# PolarTableMegaShield.net
KiCad netlist of a schematic drawn in EAGLE
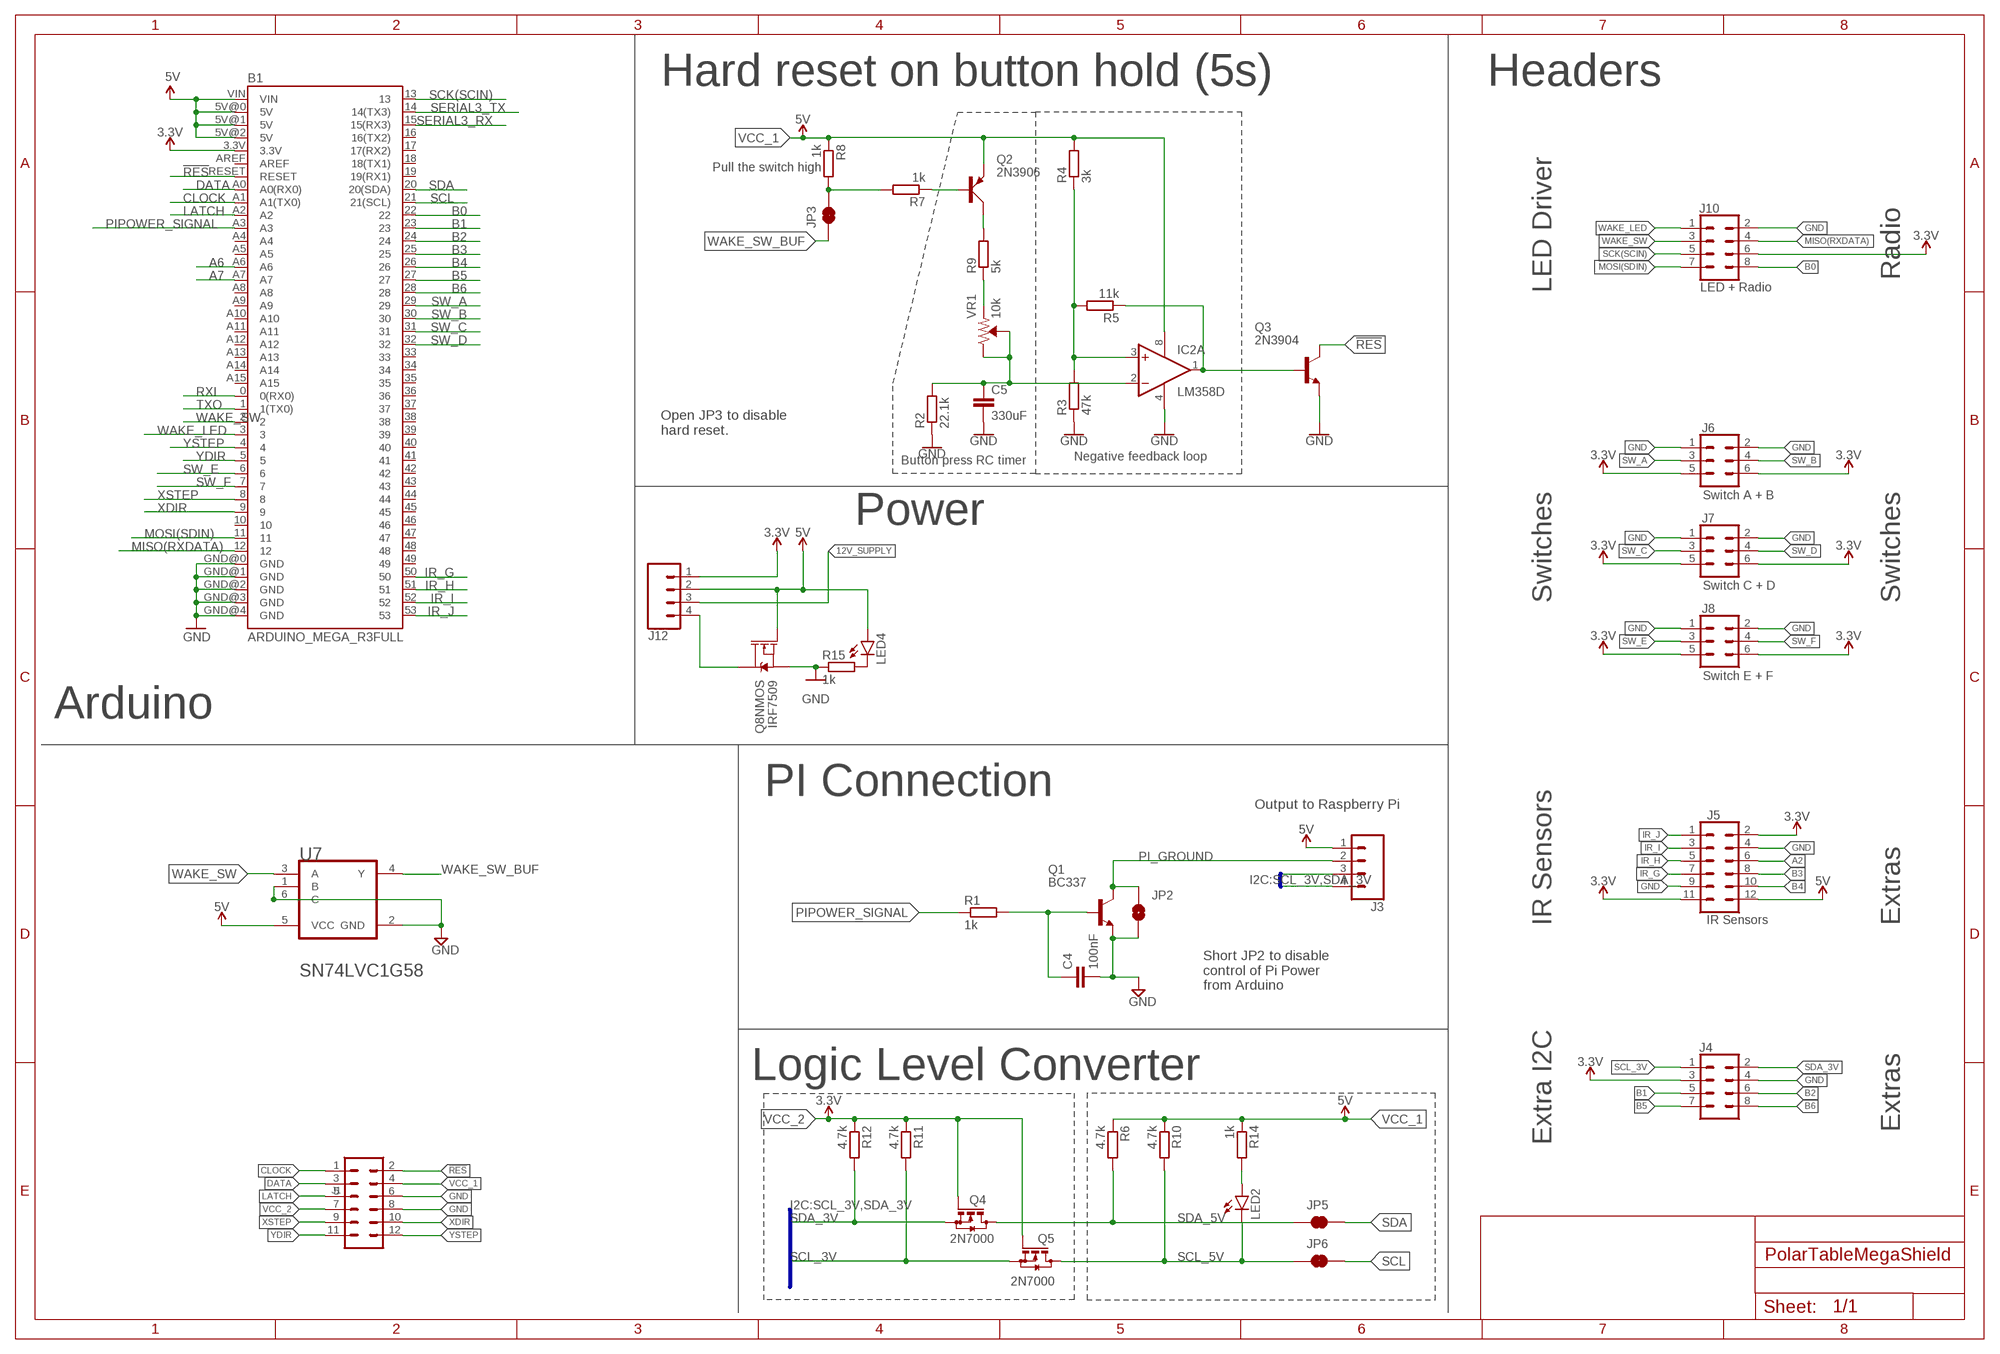
[diagram p0: schematic, sheet 1]

(export (version "E")
  (design (tool "Eeschema 10.0.6"))
  (components
    (comp (ref "B1")
      (value "ARDUINO_MEGA_R3FULL")
      (footprint "eagle-import:ARDUINO_MEGA")
      (libsource (lib "eagle-import") (part "ARDUINO_MEGA_R3FULL"))
    )
    (comp (ref "C4")
      (value "100nF")
      (footprint "eagle-import:C0805")
      (libsource (lib "eagle-import") (part "C-EUC0805"))
    )
    (comp (ref "C5")
      (value "330uF")
      (footprint "eagle-import:C0805")
      (libsource (lib "eagle-import") (part "C-EUC0805"))
    )
    (comp (ref "IC2")
      (value "LM358D")
      (footprint "eagle-import:SO08")
      (libsource (lib "eagle-import") (part "LM358D"))
    )
    (comp (ref "J1")
      (value "CONN_06X21.24MM_RA_MALE")
      (footprint "eagle-import:2X6")
      (libsource (lib "eagle-import") (part "CONN_06X21.24MM_RA_MALE"))
    )
    (comp (ref "J3")
      (value "Pi Connection")
      (footprint "eagle-import:1X04_1.24MM_RA_MALE")
      (libsource (lib "eagle-import") (part "CONN_041X04_1.24MM_RA_MALE"))
    )
    (comp (ref "J4")
      (value "CONN_04X22X4_1.24MM_RA_MALE")
      (footprint "eagle-import:2X4")
      (libsource (lib "eagle-import") (part "CONN_04X22X4_1.24MM_RA_MALE"))
    )
    (comp (ref "J5")
      (value "IR Sensors")
      (footprint "eagle-import:2X6")
      (libsource (lib "eagle-import") (part "CONN_06X21.24MM_RA_MALE"))
    )
    (comp (ref "J6")
      (value "Switch A + B")
      (footprint "eagle-import:2X3")
      (libsource (lib "eagle-import") (part "CONN_03X22X03_2.54MM_RA_MALE"))
    )
    (comp (ref "J7")
      (value "Switch C + D")
      (footprint "eagle-import:2X3")
      (libsource (lib "eagle-import") (part "CONN_03X22X03_2.54MM_RA_MALE"))
    )
    (comp (ref "J8")
      (value "Switch E + F")
      (footprint "eagle-import:2X3")
      (libsource (lib "eagle-import") (part "CONN_03X22X03_2.54MM_RA_MALE"))
    )
    (comp (ref "J10")
      (value "LED + Radio")
      (footprint "eagle-import:2X4")
      (libsource (lib "eagle-import") (part "CONN_04X22X4_1.24MM_RA_MALE"))
    )
    (comp (ref "J12")
      (value "CONN_04JST-PTH")
      (footprint "eagle-import:JST-4-PTH")
      (libsource (lib "eagle-import") (part "CONN_04JST-PTH"))
    )
    (comp (ref "JP2")
      (value "JUMPER-SMT_2_NO_SILK")
      (footprint "eagle-import:SMT-JUMPER_2_NO_SILK")
      (libsource (lib "eagle-import") (part "JUMPER-SMT_2_NO_SILK"))
    )
    (comp (ref "JP3")
      (value "Enable Hold to Reset")
      (footprint "eagle-import:SMT-JUMPER_2_NC_TRACE_SILK")
      (libsource (lib "eagle-import") (part "JUMPER-SMT_2_NC_TRACE_SILK"))
    )
    (comp (ref "JP5")
      (value "JUMPER-SMT_2_NC_TRACE_NO-SILK")
      (footprint "eagle-import:SMT-JUMPER_2_NC_TRACE_NO-SILK")
      (libsource (lib "eagle-import") (part "JUMPER-SMT_2_NC_TRACE_NO-SILK"))
    )
    (comp (ref "JP6")
      (value "JUMPER-SMT_2_NC_TRACE_NO-SILK")
      (footprint "eagle-import:SMT-JUMPER_2_NC_TRACE_NO-SILK")
      (libsource (lib "eagle-import") (part "JUMPER-SMT_2_NC_TRACE_NO-SILK"))
    )
    (comp (ref "LED2")
      (value "LEDCHIP-LED0805")
      (footprint "eagle-import:CHIP-LED0805")
      (libsource (lib "eagle-import") (part "LEDCHIP-LED0805"))
    )
    (comp (ref "LED4")
      (value "LEDCHIP-LED0805")
      (footprint "eagle-import:CHIP-LED0805")
      (libsource (lib "eagle-import") (part "LEDCHIP-LED0805"))
    )
    (comp (ref "Q1")
      (value "BC337")
      (footprint "eagle-import:TO92")
      (libsource (lib "eagle-import") (part "BC337"))
    )
    (comp (ref "Q2")
      (value "2N3906")
      (footprint "eagle-import:TO92D")
      (libsource (lib "eagle-import") (part "2N3906"))
    )
    (comp (ref "Q3")
      (value "2N3904")
      (footprint "eagle-import:TO92")
      (fields (field (name "NOTE") "Pull high until we get comparitor high output"))
      (libsource (lib "eagle-import") (part "2N3904"))
    )
    (comp (ref "Q4")
      (value "2N7000")
      (footprint "eagle-import:TO92-")
      (libsource (lib "eagle-import") (part "2N7000"))
    )
    (comp (ref "Q5")
      (value "2N7000")
      (footprint "eagle-import:TO92-")
      (libsource (lib "eagle-import") (part "2N7000"))
    )
    (comp (ref "Q8")
      (value "IRF7509")
      (footprint "eagle-import:MSOP8")
      (libsource (lib "eagle-import") (part "IRF7509"))
    )
    (comp (ref "R1")
      (value "1k")
      (footprint "eagle-import:M0805")
      (libsource (lib "eagle-import") (part "R-EU_M0805"))
    )
    (comp (ref "R2")
      (value "22.1k")
      (footprint "eagle-import:M0805")
      (libsource (lib "eagle-import") (part "R-EU_M0805"))
    )
    (comp (ref "R3")
      (value "47k")
      (footprint "eagle-import:M0805")
      (libsource (lib "eagle-import") (part "R-EU_M0805"))
    )
    (comp (ref "R4")
      (value "3k")
      (footprint "eagle-import:M0805")
      (libsource (lib "eagle-import") (part "R-EU_M0805"))
    )
    (comp (ref "R5")
      (value "11k")
      (footprint "eagle-import:M0805")
      (libsource (lib "eagle-import") (part "R-EU_M0805"))
    )
    (comp (ref "R6")
      (value "4.7k")
      (footprint "eagle-import:M0805")
      (libsource (lib "eagle-import") (part "R-EU_M0805"))
    )
    (comp (ref "R7")
      (value "1k")
      (footprint "eagle-import:M0805")
      (libsource (lib "eagle-import") (part "R-EU_M0805"))
    )
    (comp (ref "R8")
      (value "1k")
      (footprint "eagle-import:M0805")
      (fields (field (name "NOTE") "Pull the switch high"))
      (libsource (lib "eagle-import") (part "R-EU_M0805"))
    )
    (comp (ref "R9")
      (value "5k")
      (footprint "eagle-import:M0805")
      (libsource (lib "eagle-import") (part "R-EU_M0805"))
    )
    (comp (ref "R10")
      (value "4.7k")
      (footprint "eagle-import:M0805")
      (libsource (lib "eagle-import") (part "R-EU_M0805"))
    )
    (comp (ref "R11")
      (value "4.7k")
      (footprint "eagle-import:M0805")
      (libsource (lib "eagle-import") (part "R-EU_M0805"))
    )
    (comp (ref "R12")
      (value "4.7k")
      (footprint "eagle-import:M0805")
      (libsource (lib "eagle-import") (part "R-EU_M0805"))
    )
    (comp (ref "R14")
      (value "1k")
      (footprint "eagle-import:M0805")
      (libsource (lib "eagle-import") (part "R-EU_M0805"))
    )
    (comp (ref "R15")
      (value "1k")
      (footprint "eagle-import:M0805")
      (libsource (lib "eagle-import") (part "R-EU_M0805"))
    )
    (comp (ref "U7")
      (value "Buffer")
      (footprint "eagle-import:SOT363_PHILIPS")
      (libsource (lib "eagle-import") (part "TEXAS_INSTRUMENTS_SN74LVC1G58SOT363"))
    )
    (comp (ref "VR1")
      (value "10k")
      (footprint "eagle-import:TRIMPOT-PTH-3386U")
      (libsource (lib "eagle-import") (part "TRIMPOT-PTH-10MM-KNOB-1/2W-10%"))
    )
  )
  (nets
    (net (code "2") (name "/A6") (class "Default")
      (node (ref "B1") (pin "A6") (pinfunction "A6_A6") (pintype "bidirectional"))
    )
    (net (code "3") (name "/A7") (class "Default")
      (node (ref "B1") (pin "A7") (pinfunction "A7_A7") (pintype "bidirectional"))
    )
    (net (code "4") (name "/PI_GROUND") (class "Default")
      (node (ref "J3") (pin "2") (pinfunction "2_2") (pintype "passive"))
      (node (ref "JP2") (pin "1") (pinfunction "1_1") (pintype "passive"))
      (node (ref "Q1") (pin "3") (pinfunction "C_3") (pintype "passive"))
    )
    (net (code "5") (name "/RXI") (class "Default")
      (node (ref "B1") (pin "0") (pinfunction "0(RX0)_0") (pintype "bidirectional"))
    )
    (net (code "6") (name "/SCL_5V") (class "Default")
      (node (ref "JP6") (pin "1") (pinfunction "1_1") (pintype "passive"))
      (node (ref "LED2") (pin "C") (pinfunction "C_C") (pintype "passive"))
      (node (ref "Q5") (pin "3") (pinfunction "D_3") (pintype "passive"))
      (node (ref "R10") (pin "2") (pinfunction "2_2") (pintype "passive"))
    )
    (net (code "7") (name "/SDA_5V") (class "Default")
      (node (ref "JP5") (pin "1") (pinfunction "1_1") (pintype "passive"))
      (node (ref "Q4") (pin "3") (pinfunction "D_3") (pintype "passive"))
      (node (ref "R6") (pin "2") (pinfunction "2_2") (pintype "passive"))
    )
    (net (code "8") (name "/SERIAL3_RX") (class "Default")
      (node (ref "B1") (pin "15") (pinfunction "15(RX3)_15") (pintype "bidirectional"))
    )
    (net (code "9") (name "/SERIAL3_TX") (class "Default")
      (node (ref "B1") (pin "14") (pinfunction "14(TX3)_14") (pintype "bidirectional"))
    )
    (net (code "10") (name "/TXO") (class "Default")
      (node (ref "B1") (pin "1") (pinfunction "1(TX0)_1") (pintype "bidirectional"))
    )
    (net (code "12") (name "/~{RES}") (class "Default")
      (node (ref "B1") (pin "RESET") (pinfunction "RESET_RESET") (pintype "bidirectional"))
      (node (ref "J1") (pin "2") (pinfunction "2_2") (pintype "passive"))
      (node (ref "Q3") (pin "1") (pinfunction "C_1") (pintype "passive"))
    )
    (net (code "13") (name "12V_SUPPLY") (class "Default")
      (node (ref "J12") (pin "3") (pinfunction "3_3") (pintype "passive"))
    )
    (net (code "14") (name "A2") (class "Default")
      (node (ref "J5") (pin "6") (pinfunction "6_6") (pintype "passive"))
    )
    (net (code "15") (name "B0") (class "Default")
      (node (ref "B1") (pin "22") (pinfunction "22_22") (pintype "bidirectional"))
      (node (ref "J10") (pin "8") (pinfunction "8_8") (pintype "passive"))
    )
    (net (code "16") (name "B1") (class "Default")
      (node (ref "B1") (pin "23") (pinfunction "23_23") (pintype "bidirectional"))
      (node (ref "J4") (pin "5") (pinfunction "5_5") (pintype "passive"))
    )
    (net (code "17") (name "B2") (class "Default")
      (node (ref "B1") (pin "24") (pinfunction "24_24") (pintype "bidirectional"))
      (node (ref "J4") (pin "6") (pinfunction "6_6") (pintype "passive"))
    )
    (net (code "18") (name "B3") (class "Default")
      (node (ref "B1") (pin "25") (pinfunction "25_25") (pintype "bidirectional"))
      (node (ref "J5") (pin "8") (pinfunction "8_8") (pintype "passive"))
    )
    (net (code "19") (name "B4") (class "Default")
      (node (ref "B1") (pin "26") (pinfunction "26_26") (pintype "bidirectional"))
      (node (ref "J5") (pin "10") (pinfunction "10_10") (pintype "passive"))
    )
    (net (code "20") (name "B5") (class "Default")
      (node (ref "B1") (pin "27") (pinfunction "27_27") (pintype "bidirectional"))
      (node (ref "J4") (pin "7") (pinfunction "7_7") (pintype "passive"))
    )
    (net (code "21") (name "B6") (class "Default")
      (node (ref "B1") (pin "28") (pinfunction "28_28") (pintype "bidirectional"))
      (node (ref "J4") (pin "8") (pinfunction "8_8") (pintype "passive"))
    )
    (net (code "22") (name "CLOCK") (class "Default")
      (node (ref "B1") (pin "A1") (pinfunction "A1(TX0)_A1") (pintype "bidirectional"))
      (node (ref "J1") (pin "1") (pinfunction "1_1") (pintype "passive"))
    )
    (net (code "23") (name "DATA") (class "Default")
      (node (ref "B1") (pin "A0") (pinfunction "A0(RX0)_A0") (pintype "bidirectional"))
      (node (ref "J1") (pin "3") (pinfunction "3_3") (pintype "passive"))
    )
    (net (code "24") (name "GND") (class "Default")
      (node (ref "B1") (pin "GND@0") (pinfunction "GND_GND@0") (pintype "bidirectional"))
      (node (ref "B1") (pin "GND@1") (pinfunction "GND_GND@1") (pintype "bidirectional"))
      (node (ref "B1") (pin "GND@2") (pinfunction "GND_GND@2") (pintype "bidirectional"))
      (node (ref "B1") (pin "GND@3") (pinfunction "GND_GND@3") (pintype "bidirectional"))
      (node (ref "B1") (pin "GND@4") (pinfunction "GND_GND@4") (pintype "bidirectional"))
      (node (ref "C4") (pin "2") (pinfunction "2_2") (pintype "passive"))
      (node (ref "C5") (pin "2") (pinfunction "2_2") (pintype "passive"))
      (node (ref "IC2") (pin "4") (pinfunction "V-_4") (pintype "power_in"))
      (node (ref "J1") (pin "6") (pinfunction "6_6") (pintype "passive"))
      (node (ref "J1") (pin "8") (pinfunction "8_8") (pintype "passive"))
      (node (ref "J10") (pin "2") (pinfunction "2_2") (pintype "passive"))
      (node (ref "J4") (pin "4") (pinfunction "4_4") (pintype "passive"))
      (node (ref "J5") (pin "4") (pinfunction "4_4") (pintype "passive"))
      (node (ref "J5") (pin "9") (pinfunction "9_9") (pintype "passive"))
      (node (ref "J6") (pin "1") (pinfunction "1_1") (pintype "bidirectional"))
      (node (ref "J6") (pin "2") (pinfunction "2_2") (pintype "bidirectional"))
      (node (ref "J7") (pin "1") (pinfunction "1_1") (pintype "bidirectional"))
      (node (ref "J7") (pin "2") (pinfunction "2_2") (pintype "bidirectional"))
      (node (ref "J8") (pin "1") (pinfunction "1_1") (pintype "bidirectional"))
      (node (ref "J8") (pin "2") (pinfunction "2_2") (pintype "bidirectional"))
      (node (ref "JP2") (pin "2") (pinfunction "2_2") (pintype "passive"))
      (node (ref "Q1") (pin "1") (pinfunction "E_1") (pintype "passive"))
      (node (ref "Q3") (pin "3") (pinfunction "E_3") (pintype "passive"))
      (node (ref "Q8") (pin "1") (pinfunction "S_1") (pintype "bidirectional"))
      (node (ref "R15") (pin "1") (pinfunction "1_1") (pintype "passive"))
      (node (ref "R2") (pin "1") (pinfunction "1_1") (pintype "passive"))
      (node (ref "R3") (pin "1") (pinfunction "1_1") (pintype "passive"))
      (node (ref "U7") (pin "1") (pinfunction "B_1") (pintype "input"))
      (node (ref "U7") (pin "2") (pinfunction "GND_2") (pintype "power_in"))
      (node (ref "U7") (pin "6") (pinfunction "C_6") (pintype "input"))
    )
    (net (code "25") (name "IR_G") (class "Default")
      (node (ref "B1") (pin "50") (pinfunction "50_50") (pintype "bidirectional"))
      (node (ref "J5") (pin "7") (pinfunction "7_7") (pintype "passive"))
    )
    (net (code "26") (name "IR_H") (class "Default")
      (node (ref "B1") (pin "51") (pinfunction "51_51") (pintype "bidirectional"))
      (node (ref "J5") (pin "5") (pinfunction "5_5") (pintype "passive"))
    )
    (net (code "27") (name "IR_I") (class "Default")
      (node (ref "B1") (pin "52") (pinfunction "52_52") (pintype "bidirectional"))
      (node (ref "J5") (pin "3") (pinfunction "3_3") (pintype "passive"))
    )
    (net (code "28") (name "IR_J") (class "Default")
      (node (ref "B1") (pin "53") (pinfunction "53_53") (pintype "bidirectional"))
      (node (ref "J5") (pin "1") (pinfunction "1_1") (pintype "passive"))
    )
    (net (code "29") (name "LATCH") (class "Default")
      (node (ref "B1") (pin "A2") (pinfunction "A2_A2") (pintype "bidirectional"))
      (node (ref "J1") (pin "5") (pinfunction "5_5") (pintype "passive"))
    )
    (net (code "30") (name "MISO(RXDATA)") (class "Default")
      (node (ref "B1") (pin "12") (pinfunction "12_12") (pintype "bidirectional"))
      (node (ref "J10") (pin "4") (pinfunction "4_4") (pintype "passive"))
    )
    (net (code "31") (name "MOSI(SDIN)") (class "Default")
      (node (ref "B1") (pin "11") (pinfunction "11_11") (pintype "bidirectional"))
      (node (ref "J10") (pin "7") (pinfunction "7_7") (pintype "passive"))
    )
    (net (code "32") (name "Net-(IC2A-+IN)") (class "Default")
      (node (ref "IC2") (pin "3") (pinfunction "+IN_3") (pintype "input"))
      (node (ref "R3") (pin "2") (pinfunction "2_2") (pintype "passive"))
      (node (ref "R4") (pin "1") (pinfunction "1_1") (pintype "passive"))
      (node (ref "R5") (pin "2") (pinfunction "2_2") (pintype "passive"))
    )
    (net (code "33") (name "Net-(IC2A--IN)") (class "Default")
      (node (ref "C5") (pin "1") (pinfunction "1_1") (pintype "passive"))
      (node (ref "IC2") (pin "2") (pinfunction "-IN_2") (pintype "input"))
      (node (ref "R2") (pin "2") (pinfunction "2_2") (pintype "passive"))
      (node (ref "VR1") (pin "2") (pinfunction "WIPER_2") (pintype "passive"))
      (node (ref "VR1") (pin "3") (pinfunction "CW_3") (pintype "passive"))
    )
    (net (code "34") (name "Net-(IC2A-OUT)") (class "Default")
      (node (ref "IC2") (pin "1") (pinfunction "OUT_1") (pintype "output"))
      (node (ref "Q3") (pin "2") (pinfunction "B_2") (pintype "passive"))
      (node (ref "R5") (pin "1") (pinfunction "1_1") (pintype "passive"))
    )
    (net (code "35") (name "Net-(J12-Pad4)") (class "Default")
      (node (ref "J12") (pin "4") (pinfunction "4_4") (pintype "passive"))
      (node (ref "Q8") (pin "7") (pinfunction "D_7") (pintype "bidirectional"))
      (node (ref "Q8") (pin "8") (pinfunction "D_8") (pintype "bidirectional"))
    )
    (net (code "36") (name "Net-(JP3-Pad2)") (class "Default")
      (node (ref "JP3") (pin "2") (pinfunction "2_2") (pintype "passive"))
      (node (ref "R7") (pin "2") (pinfunction "2_2") (pintype "passive"))
      (node (ref "R8") (pin "2") (pinfunction "2_2") (pintype "passive"))
    )
    (net (code "37") (name "Net-(LED2-PadA)") (class "Default")
      (node (ref "LED2") (pin "A") (pinfunction "A_A") (pintype "passive"))
      (node (ref "R14") (pin "2") (pinfunction "2_2") (pintype "passive"))
    )
    (net (code "38") (name "Net-(LED4-PadC)") (class "Default")
      (node (ref "LED4") (pin "C") (pinfunction "C_C") (pintype "passive"))
      (node (ref "R15") (pin "2") (pinfunction "2_2") (pintype "passive"))
    )
    (net (code "39") (name "Net-(Q1-B)") (class "Default")
      (node (ref "C4") (pin "1") (pinfunction "1_1") (pintype "passive"))
      (node (ref "Q1") (pin "2") (pinfunction "B_2") (pintype "passive"))
      (node (ref "R1") (pin "2") (pinfunction "2_2") (pintype "passive"))
    )
    (net (code "40") (name "Net-(Q2-PadB)") (class "Default")
      (node (ref "Q2") (pin "B") (pinfunction "B_B") (pintype "passive"))
      (node (ref "R7") (pin "1") (pinfunction "1_1") (pintype "passive"))
    )
    (net (code "41") (name "Net-(Q2-PadC)") (class "Default")
      (node (ref "Q2") (pin "C") (pinfunction "C_C") (pintype "passive"))
      (node (ref "R9") (pin "2") (pinfunction "2_2") (pintype "passive"))
    )
    (net (code "42") (name "Net-(VR1-CCW)") (class "Default")
      (node (ref "R9") (pin "1") (pinfunction "1_1") (pintype "passive"))
      (node (ref "VR1") (pin "1") (pinfunction "CCW_1") (pintype "passive"))
    )
    (net (code "43") (name "PIPOWER_SIGNAL") (class "Default")
      (node (ref "B1") (pin "A3") (pinfunction "A3_A3") (pintype "bidirectional"))
      (node (ref "R1") (pin "1") (pinfunction "1_1") (pintype "passive"))
    )
    (net (code "44") (name "SCK(SCIN)") (class "Default")
      (node (ref "B1") (pin "13") (pinfunction "13_13") (pintype "bidirectional"))
      (node (ref "J10") (pin "5") (pinfunction "5_5") (pintype "passive"))
    )
    (net (code "45") (name "SCL") (class "Default")
      (node (ref "B1") (pin "21") (pinfunction "21(SCL)_21") (pintype "bidirectional"))
      (node (ref "JP6") (pin "2") (pinfunction "2_2") (pintype "passive"))
    )
    (net (code "46") (name "SCL_3V") (class "Default")
      (node (ref "J3") (pin "3") (pinfunction "3_3") (pintype "passive"))
      (node (ref "J4") (pin "1") (pinfunction "1_1") (pintype "passive"))
      (node (ref "Q5") (pin "1") (pinfunction "S_1") (pintype "passive"))
      (node (ref "R11") (pin "2") (pinfunction "2_2") (pintype "passive"))
    )
    (net (code "47") (name "SDA") (class "Default")
      (node (ref "B1") (pin "20") (pinfunction "20(SDA)_20") (pintype "bidirectional"))
      (node (ref "JP5") (pin "2") (pinfunction "2_2") (pintype "passive"))
    )
    (net (code "48") (name "SDA_3V") (class "Default")
      (node (ref "J3") (pin "4") (pinfunction "4_4") (pintype "passive"))
      (node (ref "J4") (pin "2") (pinfunction "2_2") (pintype "passive"))
      (node (ref "Q4") (pin "1") (pinfunction "S_1") (pintype "passive"))
      (node (ref "R12") (pin "2") (pinfunction "2_2") (pintype "passive"))
    )
    (net (code "49") (name "SW_A") (class "Default")
      (node (ref "B1") (pin "29") (pinfunction "29_29") (pintype "bidirectional"))
      (node (ref "J6") (pin "3") (pinfunction "3_3") (pintype "bidirectional"))
    )
    (net (code "50") (name "SW_B") (class "Default")
      (node (ref "B1") (pin "30") (pinfunction "30_30") (pintype "bidirectional"))
      (node (ref "J6") (pin "4") (pinfunction "4_4") (pintype "bidirectional"))
    )
    (net (code "51") (name "SW_C") (class "Default")
      (node (ref "B1") (pin "31") (pinfunction "31_31") (pintype "bidirectional"))
      (node (ref "J7") (pin "3") (pinfunction "3_3") (pintype "bidirectional"))
    )
    (net (code "52") (name "SW_D") (class "Default")
      (node (ref "B1") (pin "32") (pinfunction "32_32") (pintype "bidirectional"))
      (node (ref "J7") (pin "4") (pinfunction "4_4") (pintype "bidirectional"))
    )
    (net (code "53") (name "SW_E") (class "Default")
      (node (ref "B1") (pin "6") (pinfunction "6_6") (pintype "bidirectional"))
      (node (ref "J8") (pin "3") (pinfunction "3_3") (pintype "bidirectional"))
    )
    (net (code "54") (name "SW_F") (class "Default")
      (node (ref "B1") (pin "7") (pinfunction "7_7") (pintype "bidirectional"))
      (node (ref "J8") (pin "4") (pinfunction "4_4") (pintype "bidirectional"))
    )
    (net (code "55") (name "VCC_1") (class "Default")
      (node (ref "B1") (pin "5V@0") (pinfunction "5V_5V@0") (pintype "bidirectional"))
      (node (ref "B1") (pin "5V@1") (pinfunction "5V_5V@1") (pintype "bidirectional"))
      (node (ref "B1") (pin "5V@2") (pinfunction "5V_5V@2") (pintype "bidirectional"))
      (node (ref "B1") (pin "VIN") (pinfunction "VIN_VIN") (pintype "bidirectional"))
      (node (ref "IC2") (pin "8") (pinfunction "V+_8") (pintype "power_in"))
      (node (ref "J1") (pin "4") (pinfunction "4_4") (pintype "passive"))
      (node (ref "J12") (pin "2") (pinfunction "2_2") (pintype "passive"))
      (node (ref "J3") (pin "1") (pinfunction "1_1") (pintype "passive"))
      (node (ref "J5") (pin "12") (pinfunction "12_12") (pintype "passive"))
      (node (ref "LED4") (pin "A") (pinfunction "A_A") (pintype "passive"))
      (node (ref "Q2") (pin "E") (pinfunction "E_E") (pintype "passive"))
      (node (ref "Q8") (pin "2") (pinfunction "G_2") (pintype "bidirectional"))
      (node (ref "R10") (pin "1") (pinfunction "1_1") (pintype "passive"))
      (node (ref "R14") (pin "1") (pinfunction "1_1") (pintype "passive"))
      (node (ref "R4") (pin "2") (pinfunction "2_2") (pintype "passive"))
      (node (ref "R6") (pin "1") (pinfunction "1_1") (pintype "passive"))
      (node (ref "R8") (pin "1") (pinfunction "1_1") (pintype "passive"))
      (node (ref "U7") (pin "5") (pinfunction "VCC_5") (pintype "power_in"))
    )
    (net (code "56") (name "VCC_2") (class "Default")
      (node (ref "B1") (pin "3.3V") (pinfunction "3.3V_3.3V") (pintype "bidirectional"))
      (node (ref "J1") (pin "7") (pinfunction "7_7") (pintype "passive"))
      (node (ref "J10") (pin "6") (pinfunction "6_6") (pintype "passive"))
      (node (ref "J12") (pin "1") (pinfunction "1_1") (pintype "passive"))
      (node (ref "J4") (pin "3") (pinfunction "3_3") (pintype "passive"))
      (node (ref "J5") (pin "11") (pinfunction "11_11") (pintype "passive"))
      (node (ref "J5") (pin "2") (pinfunction "2_2") (pintype "passive"))
      (node (ref "J6") (pin "5") (pinfunction "5_5") (pintype "bidirectional"))
      (node (ref "J6") (pin "6") (pinfunction "6_6") (pintype "bidirectional"))
      (node (ref "J7") (pin "5") (pinfunction "5_5") (pintype "bidirectional"))
      (node (ref "J7") (pin "6") (pinfunction "6_6") (pintype "bidirectional"))
      (node (ref "J8") (pin "5") (pinfunction "5_5") (pintype "bidirectional"))
      (node (ref "J8") (pin "6") (pinfunction "6_6") (pintype "bidirectional"))
      (node (ref "Q4") (pin "2") (pinfunction "G_2") (pintype "passive"))
      (node (ref "Q5") (pin "2") (pinfunction "G_2") (pintype "passive"))
      (node (ref "R11") (pin "1") (pinfunction "1_1") (pintype "passive"))
      (node (ref "R12") (pin "1") (pinfunction "1_1") (pintype "passive"))
    )
    (net (code "57") (name "WAKE_LED") (class "Default")
      (node (ref "B1") (pin "3") (pinfunction "3_3") (pintype "bidirectional"))
      (node (ref "J10") (pin "1") (pinfunction "1_1") (pintype "passive"))
    )
    (net (code "58") (name "WAKE_SW") (class "Default")
      (node (ref "B1") (pin "2") (pinfunction "2_2") (pintype "bidirectional"))
      (node (ref "J10") (pin "3") (pinfunction "3_3") (pintype "passive"))
      (node (ref "U7") (pin "3") (pinfunction "A_3") (pintype "input"))
    )
    (net (code "59") (name "WAKE_SW_BUF") (class "Default")
      (node (ref "JP3") (pin "1") (pinfunction "1_1") (pintype "passive"))
      (node (ref "U7") (pin "4") (pinfunction "Y_4") (pintype "output"))
    )
    (net (code "60") (name "XDIR") (class "Default")
      (node (ref "B1") (pin "9") (pinfunction "9_9") (pintype "bidirectional"))
      (node (ref "J1") (pin "10") (pinfunction "10_10") (pintype "passive"))
    )
    (net (code "61") (name "XSTEP") (class "Default")
      (node (ref "B1") (pin "8") (pinfunction "8_8") (pintype "bidirectional"))
      (node (ref "J1") (pin "9") (pinfunction "9_9") (pintype "passive"))
    )
    (net (code "62") (name "YDIR") (class "Default")
      (node (ref "B1") (pin "5") (pinfunction "5_5") (pintype "bidirectional"))
      (node (ref "J1") (pin "11") (pinfunction "11_11") (pintype "passive"))
    )
    (net (code "63") (name "YSTEP") (class "Default")
      (node (ref "B1") (pin "4") (pinfunction "4_4") (pintype "bidirectional"))
      (node (ref "J1") (pin "12") (pinfunction "12_12") (pintype "passive"))
    )
    (net (code "64") (name "unconnected-(B1-16(TX2)-Pad16)") (class "Default")
      (node (ref "B1") (pin "16") (pinfunction "16(TX2)_16") (pintype "bidirectional"))
    )
    (net (code "65") (name "unconnected-(B1-17(RX2)-Pad17)") (class "Default")
      (node (ref "B1") (pin "17") (pinfunction "17(RX2)_17") (pintype "bidirectional"))
    )
    (net (code "66") (name "unconnected-(B1-18(TX1)-Pad18)") (class "Default")
      (node (ref "B1") (pin "18") (pinfunction "18(TX1)_18") (pintype "bidirectional"))
    )
    (net (code "67") (name "unconnected-(B1-19(RX1)-Pad19)") (class "Default")
      (node (ref "B1") (pin "19") (pinfunction "19(RX1)_19") (pintype "bidirectional"))
    )
    (net (code "68") (name "unconnected-(B1-Pad10)") (class "Default")
      (node (ref "B1") (pin "10") (pinfunction "10_10") (pintype "bidirectional"))
    )
    (net (code "69") (name "unconnected-(B1-Pad33)") (class "Default")
      (node (ref "B1") (pin "33") (pinfunction "33_33") (pintype "bidirectional"))
    )
    (net (code "70") (name "unconnected-(B1-Pad34)") (class "Default")
      (node (ref "B1") (pin "34") (pinfunction "34_34") (pintype "bidirectional"))
    )
    (net (code "71") (name "unconnected-(B1-Pad35)") (class "Default")
      (node (ref "B1") (pin "35") (pinfunction "35_35") (pintype "bidirectional"))
    )
    (net (code "72") (name "unconnected-(B1-Pad36)") (class "Default")
      (node (ref "B1") (pin "36") (pinfunction "36_36") (pintype "bidirectional"))
    )
    (net (code "73") (name "unconnected-(B1-Pad37)") (class "Default")
      (node (ref "B1") (pin "37") (pinfunction "37_37") (pintype "bidirectional"))
    )
    (net (code "74") (name "unconnected-(B1-Pad38)") (class "Default")
      (node (ref "B1") (pin "38") (pinfunction "38_38") (pintype "bidirectional"))
    )
    (net (code "75") (name "unconnected-(B1-Pad39)") (class "Default")
      (node (ref "B1") (pin "39") (pinfunction "39_39") (pintype "bidirectional"))
    )
    (net (code "76") (name "unconnected-(B1-Pad40)") (class "Default")
      (node (ref "B1") (pin "40") (pinfunction "40_40") (pintype "bidirectional"))
    )
    (net (code "77") (name "unconnected-(B1-Pad41)") (class "Default")
      (node (ref "B1") (pin "41") (pinfunction "41_41") (pintype "bidirectional"))
    )
    (net (code "78") (name "unconnected-(B1-Pad42)") (class "Default")
      (node (ref "B1") (pin "42") (pinfunction "42_42") (pintype "bidirectional"))
    )
    (net (code "79") (name "unconnected-(B1-Pad43)") (class "Default")
      (node (ref "B1") (pin "43") (pinfunction "43_43") (pintype "bidirectional"))
    )
    (net (code "80") (name "unconnected-(B1-Pad44)") (class "Default")
      (node (ref "B1") (pin "44") (pinfunction "44_44") (pintype "bidirectional"))
    )
    (net (code "81") (name "unconnected-(B1-Pad45)") (class "Default")
      (node (ref "B1") (pin "45") (pinfunction "45_45") (pintype "bidirectional"))
    )
    (net (code "82") (name "unconnected-(B1-Pad46)") (class "Default")
      (node (ref "B1") (pin "46") (pinfunction "46_46") (pintype "bidirectional"))
    )
    (net (code "83") (name "unconnected-(B1-Pad47)") (class "Default")
      (node (ref "B1") (pin "47") (pinfunction "47_47") (pintype "bidirectional"))
    )
    (net (code "84") (name "unconnected-(B1-Pad48)") (class "Default")
      (node (ref "B1") (pin "48") (pinfunction "48_48") (pintype "bidirectional"))
    )
    (net (code "85") (name "unconnected-(B1-Pad49)") (class "Default")
      (node (ref "B1") (pin "49") (pinfunction "49_49") (pintype "bidirectional"))
    )
    (net (code "86") (name "unconnected-(B1-PadA4)") (class "Default")
      (node (ref "B1") (pin "A4") (pinfunction "A4_A4") (pintype "bidirectional"))
    )
    (net (code "87") (name "unconnected-(B1-PadA5)") (class "Default")
      (node (ref "B1") (pin "A5") (pinfunction "A5_A5") (pintype "bidirectional"))
    )
    (net (code "88") (name "unconnected-(B1-PadA8)") (class "Default")
      (node (ref "B1") (pin "A8") (pinfunction "A8_A8") (pintype "bidirectional"))
    )
    (net (code "89") (name "unconnected-(B1-PadA9)") (class "Default")
      (node (ref "B1") (pin "A9") (pinfunction "A9_A9") (pintype "bidirectional"))
    )
    (net (code "90") (name "unconnected-(B1-PadA10)") (class "Default")
      (node (ref "B1") (pin "A10") (pinfunction "A10_A10") (pintype "bidirectional"))
    )
    (net (code "91") (name "unconnected-(B1-PadA11)") (class "Default")
      (node (ref "B1") (pin "A11") (pinfunction "A11_A11") (pintype "bidirectional"))
    )
    (net (code "92") (name "unconnected-(B1-PadA12)") (class "Default")
      (node (ref "B1") (pin "A12") (pinfunction "A12_A12") (pintype "bidirectional"))
    )
    (net (code "93") (name "unconnected-(B1-PadA13)") (class "Default")
      (node (ref "B1") (pin "A13") (pinfunction "A13_A13") (pintype "bidirectional"))
    )
    (net (code "94") (name "unconnected-(B1-PadA14)") (class "Default")
      (node (ref "B1") (pin "A14") (pinfunction "A14_A14") (pintype "bidirectional"))
    )
    (net (code "95") (name "unconnected-(B1-PadA15)") (class "Default")
      (node (ref "B1") (pin "A15") (pinfunction "A15_A15") (pintype "bidirectional"))
    )
    (net (code "96") (name "unconnected-(B1-PadAREF)") (class "Default")
      (node (ref "B1") (pin "AREF") (pinfunction "AREF_AREF") (pintype "bidirectional"))
    )
  )
)
